# STM32G4.net
KiCad netlist of a schematic drawn in Altium Designer
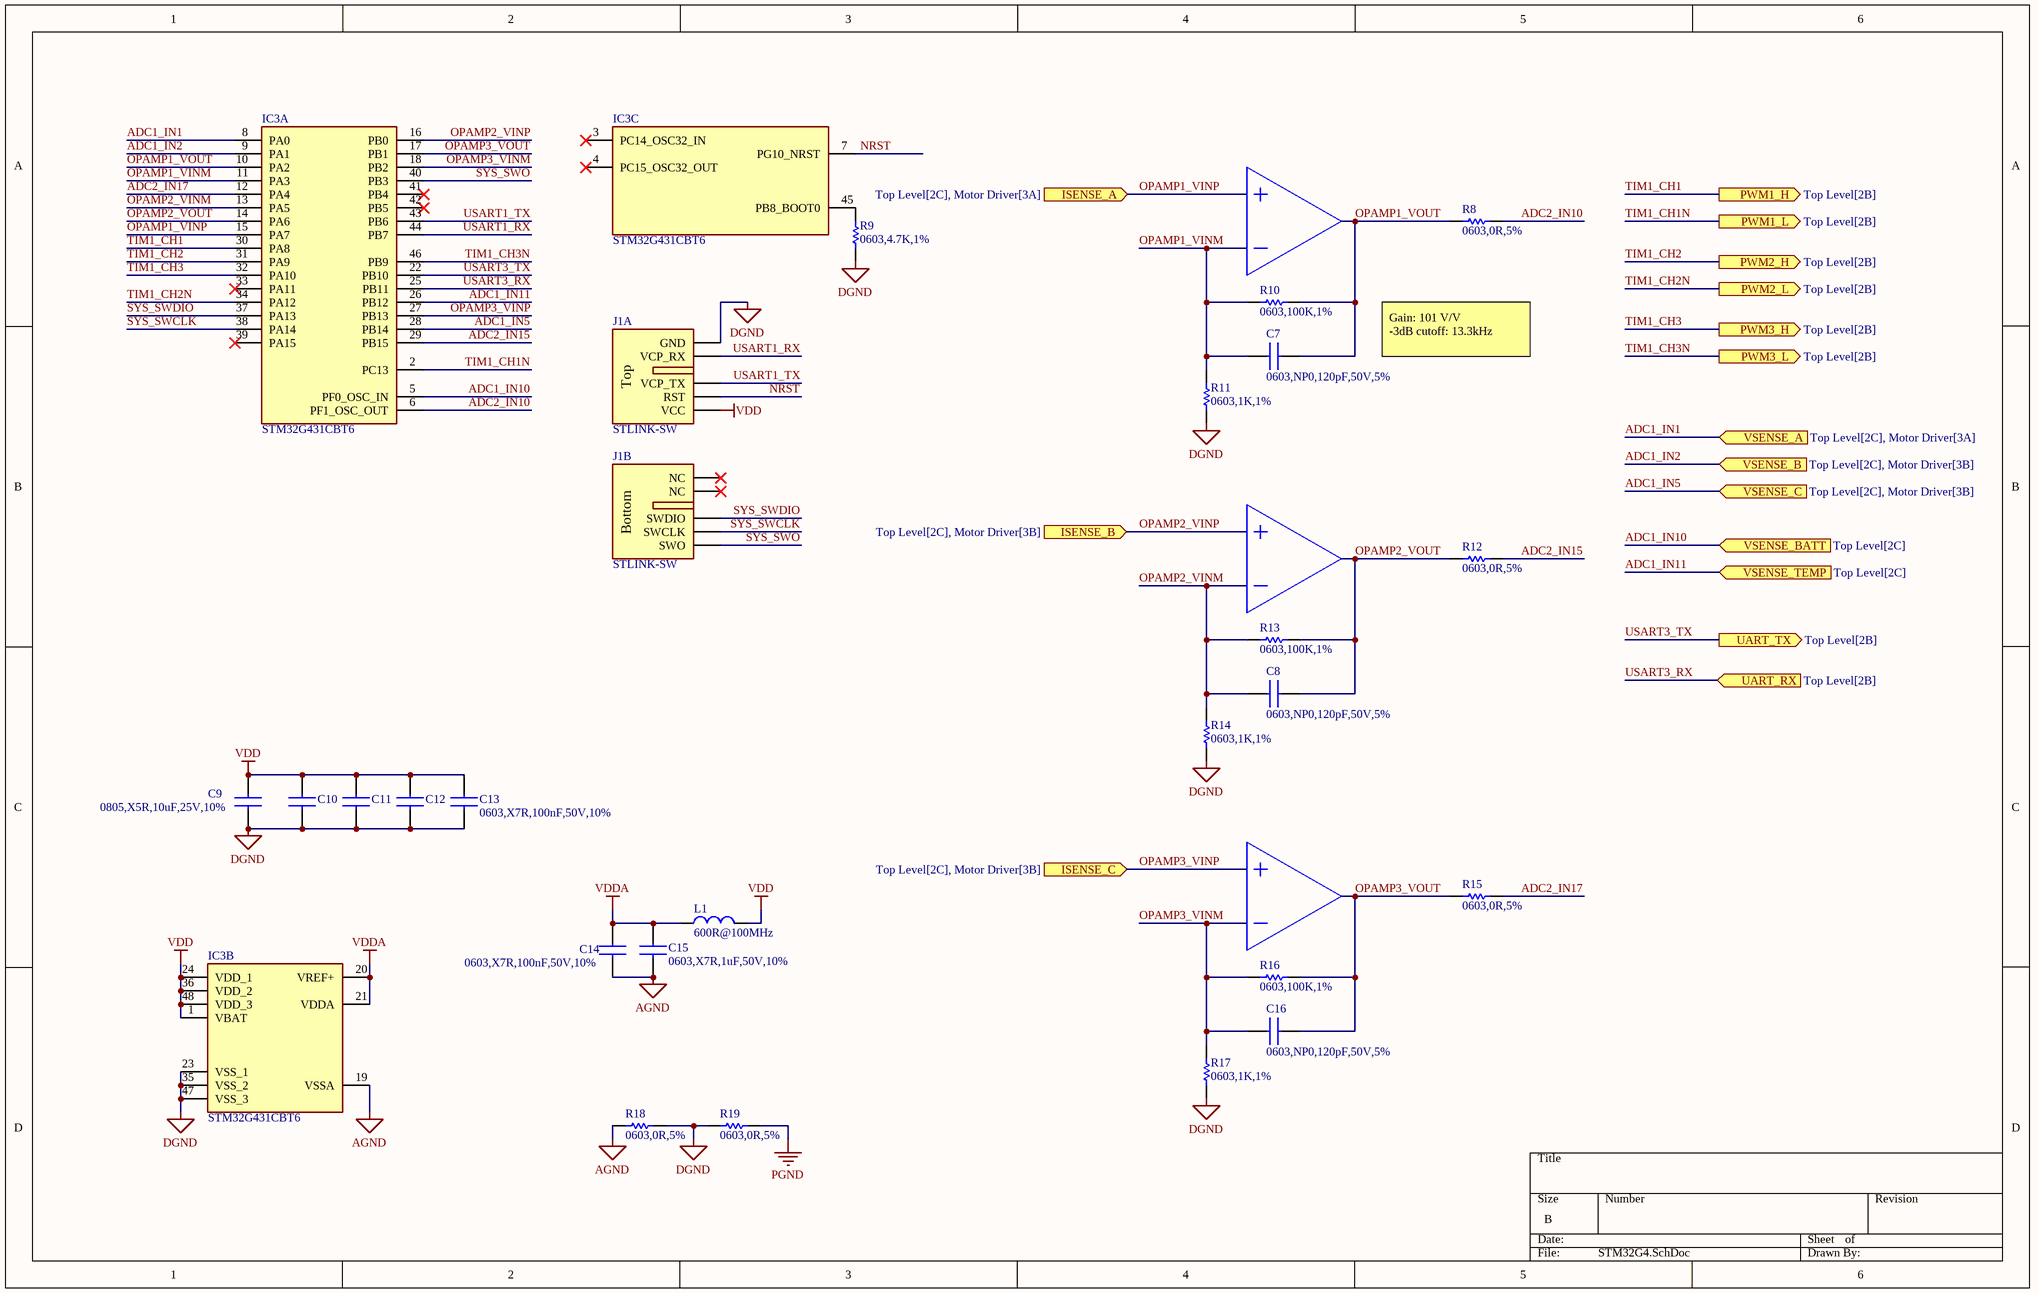
[diagram p0: STM32G4.SchDoc]

(export (version "E")
  (design (tool "Eeschema 10.0.6"))
  (components
    (comp (ref "C7")
      (value "0603,NP0,120pF,50V,5%")
      (footprint "CAPC1608X90N")
      (description "50V 120pF NP0 ±5% 0603 Multilayer Ceramic Capacitors MLCC - SMD/SMT ROHS")
      (fields
        (field (name "MANUFACTURER_PART_NUMBER") "CC0603JRNPO9BN121")
        (field (name "MOUSER PART NUMBER") "603-CC603KRX7R9BB104")
      )
      (libsource (lib "ESC") (part "CC0603JRNPO9BN121"))
    )
    (comp (ref "C8")
      (value "0603,NP0,120pF,50V,5%")
      (footprint "CAPC1608X90N")
      (description "50V 120pF NP0 ±5% 0603 Multilayer Ceramic Capacitors MLCC - SMD/SMT ROHS")
      (fields
        (field (name "MANUFACTURER_PART_NUMBER") "CC0603JRNPO9BN121")
        (field (name "MOUSER PART NUMBER") "603-CC603KRX7R9BB104")
      )
      (libsource (lib "ESC") (part "CC0603JRNPO9BN121"))
    )
    (comp (ref "C9")
      (value "0805,X5R,10uF,25V,10%")
      (footprint "CAPC2012X145N")
      (description "10 µF ±10% 25V Ceramic Capacitor X5R 0805 (2012 Metric)")
      (fields
        (field (name "MANUFACTURER_PART_NUMBER") "CC0805KKX5R8BB106")
        (field (name "MOUSER PART NUMBER") "603-CC805KKX5R8BB106")
      )
      (libsource (lib "ESC") (part "CC0805KKX5R8BB106"))
    )
    (comp (ref "C10")
      (value "0603,X7R,100nF,50V,10%")
      (footprint "CAPC1608X90N")
      (description "50V 100nF X7R ±10% 0603 Multilayer Ceramic Capacitors MLCC - SMD/SMT ROHS")
      (fields
        (field (name "MANUFACTURER_PART_NUMBER") "CC0603KRX7R9BB104")
        (field (name "MOUSER PART NUMBER") "603-CC603KRX7R9BB104")
      )
      (libsource (lib "ESC") (part "CC0603KRX7R9BB104"))
    )
    (comp (ref "C11")
      (value "0603,X7R,100nF,50V,10%")
      (footprint "CAPC1608X90N")
      (description "50V 100nF X7R ±10% 0603 Multilayer Ceramic Capacitors MLCC - SMD/SMT ROHS")
      (fields
        (field (name "MANUFACTURER_PART_NUMBER") "CC0603KRX7R9BB104")
        (field (name "MOUSER PART NUMBER") "603-CC603KRX7R9BB104")
      )
      (libsource (lib "ESC") (part "CC0603KRX7R9BB104"))
    )
    (comp (ref "C12")
      (value "0603,X7R,100nF,50V,10%")
      (footprint "CAPC1608X90N")
      (description "50V 100nF X7R ±10% 0603 Multilayer Ceramic Capacitors MLCC - SMD/SMT ROHS")
      (fields
        (field (name "MANUFACTURER_PART_NUMBER") "CC0603KRX7R9BB104")
        (field (name "MOUSER PART NUMBER") "603-CC603KRX7R9BB104")
      )
      (libsource (lib "ESC") (part "CC0603KRX7R9BB104"))
    )
    (comp (ref "C13")
      (value "0603,X7R,100nF,50V,10%")
      (footprint "CAPC1608X90N")
      (description "50V 100nF X7R ±10% 0603 Multilayer Ceramic Capacitors MLCC - SMD/SMT ROHS")
      (fields
        (field (name "MANUFACTURER_PART_NUMBER") "CC0603KRX7R9BB104")
        (field (name "MOUSER PART NUMBER") "603-CC603KRX7R9BB104")
      )
      (libsource (lib "ESC") (part "CC0603KRX7R9BB104"))
    )
    (comp (ref "C14")
      (value "0603,X7R,100nF,50V,10%")
      (footprint "CAPC1608X90N")
      (description "50V 100nF X7R ±10% 0603 Multilayer Ceramic Capacitors MLCC - SMD/SMT ROHS")
      (fields
        (field (name "MANUFACTURER_PART_NUMBER") "CC0603KRX7R9BB104")
        (field (name "MOUSER PART NUMBER") "603-CC603KRX7R9BB104")
      )
      (libsource (lib "ESC") (part "CC0603KRX7R9BB104"))
    )
    (comp (ref "C15")
      (value "0603,X7R,1uF,50V,10%")
      (footprint "CAPC1608X90N")
      (description "50V 1uF X7R ±10% 0603 Multilayer Ceramic Capacitors MLCC - SMD/SMT ROHS")
      (fields
        (field (name "MANUFACTURER_PART_NUMBER") "CC0603KRX7R9BB105")
        (field (name "MOUSER PART NUMBER") "603-CC603KRX7R9BB105")
      )
      (libsource (lib "ESC") (part "CC0603KRX7R9BB105"))
    )
    (comp (ref "C16")
      (value "0603,NP0,120pF,50V,5%")
      (footprint "CAPC1608X90N")
      (description "50V 120pF NP0 ±5% 0603 Multilayer Ceramic Capacitors MLCC - SMD/SMT ROHS")
      (fields
        (field (name "MANUFACTURER_PART_NUMBER") "CC0603JRNPO9BN121")
        (field (name "MOUSER PART NUMBER") "603-CC603KRX7R9BB104")
      )
      (libsource (lib "ESC") (part "CC0603JRNPO9BN121"))
    )
    (comp (ref "IC3")
      (value "STM32G431CBT6")
      (footprint "QFP50P900X900X160-48N")
      (fields (field (name "MOUSER PART NUMBER") "511-STM32G431CBT6") (field (name "LCSC PART #") "C529355"))
      (libsource (lib "ESC") (part "STM32G431CBT6"))
    )
    (comp (ref "J1")
      (value "STLINK-SW")
      (footprint "Valkyrie ESC:009159010061911")
      (description "SSL Connector 10 Position Adapter, Bridge Board to Board - Card Edge 0.079\" (2.00mm)")
      (libsource (lib "ESC") (part "STLINK-SW"))
    )
    (comp (ref "L1")
      (value "600R@100MHz")
      (footprint "L0603")
      (description "380mΩ ±25% 600Ω@100MHz 0603 Ferrite Beads ROHS")
      (fields (field (name "LCSC PART #") "C19330"))
      (libsource (lib "ESC") (part "BLM18AG601SN1D"))
    )
    (comp (ref "R8")
      (value "0603,0R,5%")
      (footprint "RESC1608X55N")
      (description "100mW Thick Film Resistor 75V ±5% 0Ω 0603 Chip Resistor - Surface Mount ROHS")
      (fields
        (field (name "MANUFACTURER_PART_NUMBER") "RC0603JR-070RL")
        (field (name "LCSC PART #") "C95177")
      )
      (libsource (lib "ESC") (part "RC0603JR-070RL"))
    )
    (comp (ref "R9")
      (value "0603,4.7K,1%")
      (footprint "RESC1608X55N")
      (description "100mW Thick Film Resistor 75V ±100ppm/℃ ±1% 4.7kΩ 0603 Chip Resistor - Surface Mount ROHS")
      (fields
        (field (name "MANUFACTURER_PART_NUMBER") "RC0603FR-074K7L")
        (field (name "LCSC PART #") "C99782")
      )
      (libsource (lib "ESC") (part "RC0603FR-074K7L"))
    )
    (comp (ref "R10")
      (value "0603,100K,1%")
      (footprint "RESC1608X55N")
      (description "100mW Thick Film Resistor 75V ±100ppm/℃ ±1% 100kΩ 0603 Chip Resistor - Surface Mount ROHS")
      (fields
        (field (name "MANUFACTURER_PART_NUMBER") "RC0603FR-07100KL")
        (field (name "LCSC PART #") "C14675")
      )
      (libsource (lib "ESC") (part "RC0603FR-07100KL"))
    )
    (comp (ref "R11")
      (value "0603,1K,1%")
      (footprint "RESC1608X55N")
      (description "100mW Thick Film Resistor 75V ±100ppm/℃ ±1% 1kΩ 0603 Chip Resistor - Surface Mount ROHS")
      (fields
        (field (name "MANUFACTURER_PART_NUMBER") "RC0603FR-071KL")
        (field (name "LCSC PART #") "C22548")
      )
      (libsource (lib "ESC") (part "RC0603FR-071KL"))
    )
    (comp (ref "R12")
      (value "0603,0R,5%")
      (footprint "RESC1608X55N")
      (description "100mW Thick Film Resistor 75V ±5% 0Ω 0603 Chip Resistor - Surface Mount ROHS")
      (fields
        (field (name "MANUFACTURER_PART_NUMBER") "RC0603JR-070RL")
        (field (name "LCSC PART #") "C95177")
      )
      (libsource (lib "ESC") (part "RC0603JR-070RL"))
    )
    (comp (ref "R13")
      (value "0603,100K,1%")
      (footprint "RESC1608X55N")
      (description "100mW Thick Film Resistor 75V ±100ppm/℃ ±1% 100kΩ 0603 Chip Resistor - Surface Mount ROHS")
      (fields
        (field (name "MANUFACTURER_PART_NUMBER") "RC0603FR-07100KL")
        (field (name "LCSC PART #") "C14675")
      )
      (libsource (lib "ESC") (part "RC0603FR-07100KL"))
    )
    (comp (ref "R14")
      (value "0603,1K,1%")
      (footprint "RESC1608X55N")
      (description "100mW Thick Film Resistor 75V ±100ppm/℃ ±1% 1kΩ 0603 Chip Resistor - Surface Mount ROHS")
      (fields
        (field (name "MANUFACTURER_PART_NUMBER") "RC0603FR-071KL")
        (field (name "LCSC PART #") "C22548")
      )
      (libsource (lib "ESC") (part "RC0603FR-071KL"))
    )
    (comp (ref "R15")
      (value "0603,0R,5%")
      (footprint "RESC1608X55N")
      (description "100mW Thick Film Resistor 75V ±5% 0Ω 0603 Chip Resistor - Surface Mount ROHS")
      (fields
        (field (name "MANUFACTURER_PART_NUMBER") "RC0603JR-070RL")
        (field (name "LCSC PART #") "C95177")
      )
      (libsource (lib "ESC") (part "RC0603JR-070RL"))
    )
    (comp (ref "R16")
      (value "0603,100K,1%")
      (footprint "RESC1608X55N")
      (description "100mW Thick Film Resistor 75V ±100ppm/℃ ±1% 100kΩ 0603 Chip Resistor - Surface Mount ROHS")
      (fields
        (field (name "MANUFACTURER_PART_NUMBER") "RC0603FR-07100KL")
        (field (name "LCSC PART #") "C14675")
      )
      (libsource (lib "ESC") (part "RC0603FR-07100KL"))
    )
    (comp (ref "R17")
      (value "0603,1K,1%")
      (footprint "RESC1608X55N")
      (description "100mW Thick Film Resistor 75V ±100ppm/℃ ±1% 1kΩ 0603 Chip Resistor - Surface Mount ROHS")
      (fields
        (field (name "MANUFACTURER_PART_NUMBER") "RC0603FR-071KL")
        (field (name "LCSC PART #") "C22548")
      )
      (libsource (lib "ESC") (part "RC0603FR-071KL"))
    )
    (comp (ref "R18")
      (value "0603,0R,5%")
      (footprint "RESC1608X55N")
      (description "100mW Thick Film Resistor 75V ±5% 0Ω 0603 Chip Resistor - Surface Mount ROHS")
      (fields
        (field (name "MANUFACTURER_PART_NUMBER") "RC0603JR-070RL")
        (field (name "LCSC PART #") "C95177")
      )
      (libsource (lib "ESC") (part "RC0603JR-070RL"))
    )
    (comp (ref "R19")
      (value "0603,0R,5%")
      (footprint "RESC1608X55N")
      (description "100mW Thick Film Resistor 75V ±5% 0Ω 0603 Chip Resistor - Surface Mount ROHS")
      (fields
        (field (name "MANUFACTURER_PART_NUMBER") "RC0603JR-070RL")
        (field (name "LCSC PART #") "C95177")
      )
      (libsource (lib "ESC") (part "RC0603JR-070RL"))
    )
  )
  (nets
    (net (code "1") (name "/ADC1_IN1") (class "Default")
      (node (ref "IC3") (pin "8") (pinfunction "PA0_8") (pintype "passive"))
    )
    (net (code "2") (name "/ADC1_IN2") (class "Default")
      (node (ref "IC3") (pin "9") (pinfunction "PA1_9") (pintype "passive"))
    )
    (net (code "3") (name "/ADC1_IN5") (class "Default")
      (node (ref "IC3") (pin "28") (pinfunction "PB14_28") (pintype "passive"))
    )
    (net (code "4") (name "/ADC1_IN10") (class "Default")
      (node (ref "IC3") (pin "5") (pinfunction "PF0_OSC_IN_5") (pintype "passive"))
    )
    (net (code "5") (name "/ADC1_IN11") (class "Default")
      (node (ref "IC3") (pin "26") (pinfunction "PB12_26") (pintype "passive"))
    )
    (net (code "6") (name "/ADC2_IN10") (class "Default")
      (node (ref "IC3") (pin "6") (pinfunction "PF1_OSC_OUT_6") (pintype "passive"))
      (node (ref "R8") (pin "2") (pinfunction "2_2") (pintype "passive"))
    )
    (net (code "7") (name "/ADC2_IN15") (class "Default")
      (node (ref "IC3") (pin "29") (pinfunction "PB15_29") (pintype "passive"))
      (node (ref "R12") (pin "2") (pinfunction "2_2") (pintype "passive"))
    )
    (net (code "8") (name "/ADC2_IN17") (class "Default")
      (node (ref "IC3") (pin "12") (pinfunction "PA4_12") (pintype "passive"))
      (node (ref "R15") (pin "2") (pinfunction "2_2") (pintype "passive"))
    )
    (net (code "9") (name "/NRST") (class "Default")
      (node (ref "IC3") (pin "7") (pinfunction "PG10_NRST_7") (pintype "passive"))
      (node (ref "J1") (pin "4") (pinfunction "RST_4") (pintype "passive"))
    )
    (net (code "10") (name "/OPAMP1_VINM") (class "Default")
      (node (ref "C7") (pin "1") (pinfunction "1_1") (pintype "passive"))
      (node (ref "IC3") (pin "11") (pinfunction "PA3_11") (pintype "passive"))
      (node (ref "R10") (pin "1") (pinfunction "1_1") (pintype "passive"))
      (node (ref "R11") (pin "2") (pinfunction "2_2") (pintype "passive"))
    )
    (net (code "11") (name "/OPAMP1_VINP") (class "Default")
      (node (ref "IC3") (pin "15") (pinfunction "PA7_15") (pintype "passive"))
    )
    (net (code "12") (name "/OPAMP1_VOUT") (class "Default")
      (node (ref "C7") (pin "2") (pinfunction "2_2") (pintype "passive"))
      (node (ref "IC3") (pin "10") (pinfunction "PA2_10") (pintype "passive"))
      (node (ref "R10") (pin "2") (pinfunction "2_2") (pintype "passive"))
      (node (ref "R8") (pin "1") (pinfunction "1_1") (pintype "passive"))
    )
    (net (code "13") (name "/OPAMP2_VINM") (class "Default")
      (node (ref "C8") (pin "1") (pinfunction "1_1") (pintype "passive"))
      (node (ref "IC3") (pin "13") (pinfunction "PA5_13") (pintype "passive"))
      (node (ref "R13") (pin "1") (pinfunction "1_1") (pintype "passive"))
      (node (ref "R14") (pin "2") (pinfunction "2_2") (pintype "passive"))
    )
    (net (code "14") (name "/OPAMP2_VINP") (class "Default")
      (node (ref "IC3") (pin "16") (pinfunction "PB0_16") (pintype "passive"))
    )
    (net (code "15") (name "/OPAMP2_VOUT") (class "Default")
      (node (ref "C8") (pin "2") (pinfunction "2_2") (pintype "passive"))
      (node (ref "IC3") (pin "14") (pinfunction "PA6_14") (pintype "passive"))
      (node (ref "R12") (pin "1") (pinfunction "1_1") (pintype "passive"))
      (node (ref "R13") (pin "2") (pinfunction "2_2") (pintype "passive"))
    )
    (net (code "16") (name "/OPAMP3_VINM") (class "Default")
      (node (ref "C16") (pin "1") (pinfunction "1_1") (pintype "passive"))
      (node (ref "IC3") (pin "18") (pinfunction "PB2_18") (pintype "passive"))
      (node (ref "R16") (pin "1") (pinfunction "1_1") (pintype "passive"))
      (node (ref "R17") (pin "2") (pinfunction "2_2") (pintype "passive"))
    )
    (net (code "17") (name "/OPAMP3_VINP") (class "Default")
      (node (ref "IC3") (pin "27") (pinfunction "PB13_27") (pintype "passive"))
    )
    (net (code "18") (name "/OPAMP3_VOUT") (class "Default")
      (node (ref "C16") (pin "2") (pinfunction "2_2") (pintype "passive"))
      (node (ref "IC3") (pin "17") (pinfunction "PB1_17") (pintype "passive"))
      (node (ref "R15") (pin "1") (pinfunction "1_1") (pintype "passive"))
      (node (ref "R16") (pin "2") (pinfunction "2_2") (pintype "passive"))
    )
    (net (code "19") (name "/SYS_SWCLK") (class "Default")
      (node (ref "IC3") (pin "38") (pinfunction "PA14_38") (pintype "passive"))
      (node (ref "J1") (pin "9") (pinfunction "SWCLK_9") (pintype "passive"))
    )
    (net (code "20") (name "/SYS_SWDIO") (class "Default")
      (node (ref "IC3") (pin "37") (pinfunction "PA13_37") (pintype "passive"))
      (node (ref "J1") (pin "8") (pinfunction "SWDIO_8") (pintype "passive"))
    )
    (net (code "21") (name "/SYS_SWO") (class "Default")
      (node (ref "IC3") (pin "40") (pinfunction "PB3_40") (pintype "passive"))
      (node (ref "J1") (pin "10") (pinfunction "SWO_10") (pintype "passive"))
    )
    (net (code "22") (name "/TIM1_CH1") (class "Default")
      (node (ref "IC3") (pin "30") (pinfunction "PA8_30") (pintype "passive"))
    )
    (net (code "23") (name "/TIM1_CH1N") (class "Default")
      (node (ref "IC3") (pin "2") (pinfunction "PC13_2") (pintype "passive"))
    )
    (net (code "24") (name "/TIM1_CH2") (class "Default")
      (node (ref "IC3") (pin "31") (pinfunction "PA9_31") (pintype "passive"))
    )
    (net (code "25") (name "/TIM1_CH2N") (class "Default")
      (node (ref "IC3") (pin "34") (pinfunction "PA12_34") (pintype "passive"))
    )
    (net (code "26") (name "/TIM1_CH3") (class "Default")
      (node (ref "IC3") (pin "32") (pinfunction "PA10_32") (pintype "passive"))
    )
    (net (code "27") (name "/TIM1_CH3N") (class "Default")
      (node (ref "IC3") (pin "46") (pinfunction "PB9_46") (pintype "passive"))
    )
    (net (code "28") (name "/USART1_RX") (class "Default")
      (node (ref "IC3") (pin "44") (pinfunction "PB7_44") (pintype "passive"))
      (node (ref "J1") (pin "2") (pinfunction "VCP_RX_2") (pintype "passive"))
    )
    (net (code "29") (name "/USART1_TX") (class "Default")
      (node (ref "IC3") (pin "43") (pinfunction "PB6_43") (pintype "passive"))
      (node (ref "J1") (pin "3") (pinfunction "VCP_TX_3") (pintype "passive"))
    )
    (net (code "30") (name "/USART3_RX") (class "Default")
      (node (ref "IC3") (pin "25") (pinfunction "PB11_25") (pintype "passive"))
    )
    (net (code "31") (name "/USART3_TX") (class "Default")
      (node (ref "IC3") (pin "22") (pinfunction "PB10_22") (pintype "passive"))
    )
    (net (code "32") (name "AGND") (class "Default")
      (node (ref "C14") (pin "1") (pinfunction "1_1") (pintype "passive"))
      (node (ref "C15") (pin "1") (pinfunction "1_1") (pintype "passive"))
      (node (ref "IC3") (pin "19") (pinfunction "VSSA_19") (pintype "passive"))
      (node (ref "R18") (pin "1") (pinfunction "1_1") (pintype "passive"))
    )
    (net (code "33") (name "DGND") (class "Default")
      (node (ref "C10") (pin "1") (pinfunction "1_1") (pintype "passive"))
      (node (ref "C11") (pin "1") (pinfunction "1_1") (pintype "passive"))
      (node (ref "C12") (pin "1") (pinfunction "1_1") (pintype "passive"))
      (node (ref "C13") (pin "1") (pinfunction "1_1") (pintype "passive"))
      (node (ref "C9") (pin "1") (pinfunction "1_1") (pintype "passive"))
      (node (ref "IC3") (pin "23") (pinfunction "VSS_1_23") (pintype "passive"))
      (node (ref "IC3") (pin "35") (pinfunction "VSS_2_35") (pintype "passive"))
      (node (ref "IC3") (pin "47") (pinfunction "VSS_3_47") (pintype "passive"))
      (node (ref "J1") (pin "1") (pinfunction "GND_1") (pintype "passive"))
      (node (ref "R11") (pin "1") (pinfunction "1_1") (pintype "passive"))
      (node (ref "R14") (pin "1") (pinfunction "1_1") (pintype "passive"))
      (node (ref "R17") (pin "1") (pinfunction "1_1") (pintype "passive"))
      (node (ref "R18") (pin "2") (pinfunction "2_2") (pintype "passive"))
      (node (ref "R19") (pin "1") (pinfunction "1_1") (pintype "passive"))
      (node (ref "R9") (pin "1") (pinfunction "1_1") (pintype "passive"))
    )
    (net (code "34") (name "Net-(IC3C-PB8_BOOT0)") (class "Default")
      (node (ref "IC3") (pin "45") (pinfunction "PB8_BOOT0_45") (pintype "passive"))
      (node (ref "R9") (pin "2") (pinfunction "2_2") (pintype "passive"))
    )
    (net (code "35") (name "PGND") (class "Default")
      (node (ref "R19") (pin "2") (pinfunction "2_2") (pintype "passive"))
    )
    (net (code "36") (name "VDD") (class "Default")
      (node (ref "C10") (pin "2") (pinfunction "2_2") (pintype "passive"))
      (node (ref "C11") (pin "2") (pinfunction "2_2") (pintype "passive"))
      (node (ref "C12") (pin "2") (pinfunction "2_2") (pintype "passive"))
      (node (ref "C13") (pin "2") (pinfunction "2_2") (pintype "passive"))
      (node (ref "C9") (pin "2") (pinfunction "2_2") (pintype "passive"))
      (node (ref "IC3") (pin "1") (pinfunction "VBAT_1") (pintype "passive"))
      (node (ref "IC3") (pin "24") (pinfunction "VDD_1_24") (pintype "passive"))
      (node (ref "IC3") (pin "36") (pinfunction "VDD_2_36") (pintype "passive"))
      (node (ref "IC3") (pin "48") (pinfunction "VDD_3_48") (pintype "passive"))
      (node (ref "J1") (pin "5") (pinfunction "VCC_5") (pintype "passive"))
      (node (ref "L1") (pin "2") (pinfunction "2_2") (pintype "passive"))
    )
    (net (code "37") (name "VDDA") (class "Default")
      (node (ref "C14") (pin "2") (pinfunction "2_2") (pintype "passive"))
      (node (ref "C15") (pin "2") (pinfunction "2_2") (pintype "passive"))
      (node (ref "IC3") (pin "20") (pinfunction "VREF+_20") (pintype "passive"))
      (node (ref "IC3") (pin "21") (pinfunction "VDDA_21") (pintype "passive"))
      (node (ref "L1") (pin "1") (pinfunction "1_1") (pintype "passive"))
    )
    (net (code "38") (name "unconnected-(IC3A-PA11-Pad33)") (class "Default")
      (node (ref "IC3") (pin "33") (pinfunction "PA11_33") (pintype "passive+no_connect"))
    )
    (net (code "39") (name "unconnected-(IC3A-PA15-Pad39)") (class "Default")
      (node (ref "IC3") (pin "39") (pinfunction "PA15_39") (pintype "passive+no_connect"))
    )
    (net (code "40") (name "unconnected-(IC3A-PB4-Pad41)") (class "Default")
      (node (ref "IC3") (pin "41") (pinfunction "PB4_41") (pintype "passive+no_connect"))
    )
    (net (code "41") (name "unconnected-(IC3A-PB5-Pad42)") (class "Default")
      (node (ref "IC3") (pin "42") (pinfunction "PB5_42") (pintype "passive+no_connect"))
    )
    (net (code "42") (name "unconnected-(IC3C-PC14_OSC32_IN-Pad3)") (class "Default")
      (node (ref "IC3") (pin "3") (pinfunction "PC14_OSC32_IN_3") (pintype "passive+no_connect"))
    )
    (net (code "43") (name "unconnected-(IC3C-PC15_OSC32_OUT-Pad4)") (class "Default")
      (node (ref "IC3") (pin "4") (pinfunction "PC15_OSC32_OUT_4") (pintype "passive+no_connect"))
    )
    (net (code "44") (name "unconnected-(J1B-NC-Pad6)") (class "Default")
      (node (ref "J1") (pin "6") (pinfunction "NC_6") (pintype "passive+no_connect"))
    )
    (net (code "45") (name "unconnected-(J1B-NC-Pad7)") (class "Default")
      (node (ref "J1") (pin "7") (pinfunction "NC_7") (pintype "passive+no_connect"))
    )
  )
)
